# 12V-2A-buck.net
KiCad netlist of a schematic drawn in Altium Designer
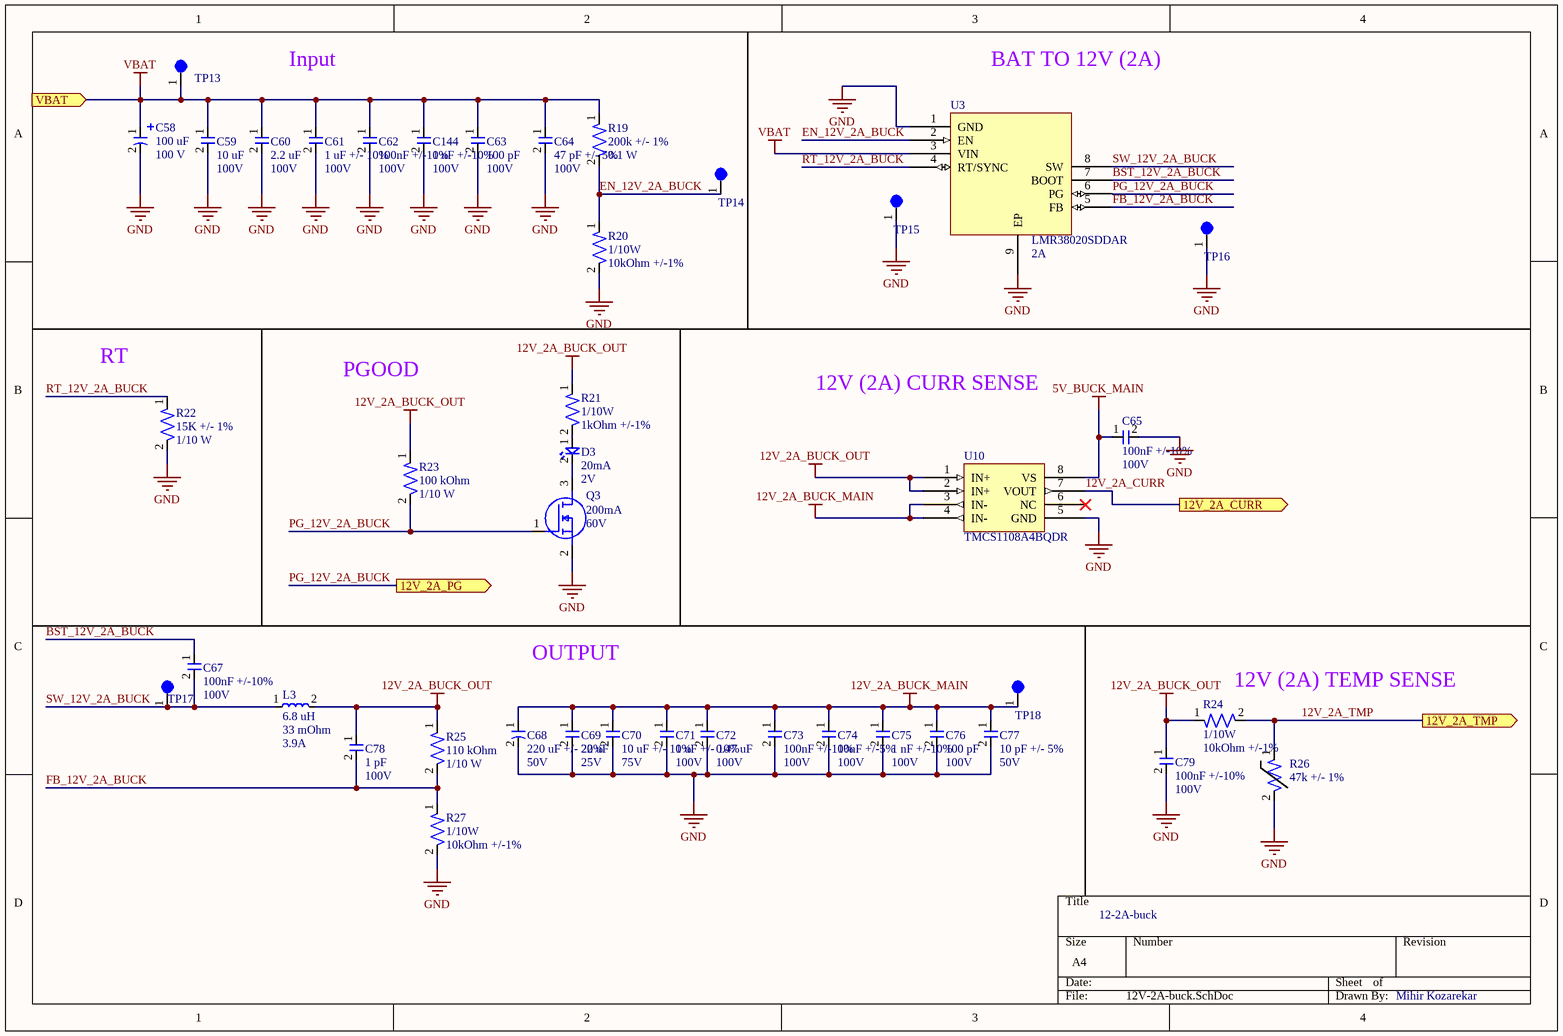
[diagram p0: 12V-2A-buck.SchDoc]

(export (version "E")
  (design (tool "Eeschema 10.0.6"))
  (components
    (comp (ref "C58")
      (value "100SEV100M12.5X16")
      (footprint "ELEC-100U-0001")
      (description "100 µF 100 V Aluminum Electrolytic Capacitors Radial, Can - SMD 2000 Hrs @ 85°C")
      (fields
        (field (name "MANUFACTURER") "Rubycon")
        (field (name "TOLERANCE") "+/- 20%")
        (field (name "CAPACITANCE") "100 uF")
        (field (name "VOLTAGE") "100 V")
      )
      (libsource (lib "MasterLib") (part "ELEC-100U-0001"))
    )
    (comp (ref "C59")
      (value "GRM32EC72A106KE05L")
      (footprint "CAP-1210")
      (description "10 µF ±10% 100V Ceramic Capacitor X7S 1210 (3225 Metric)")
      (fields (field (name "CAPCITANCE") "10 uF") (field (name "VOLTAGE RATING") "100V"))
      (libsource (lib "MasterLib") (part "CAP-10U-0003"))
    )
    (comp (ref "C60")
      (value "CL31B225KCHSNNE")
      (footprint "CAP-1206")
      (description "2.2 µF ±10% 100V Ceramic Capacitor X7R 1206 (3216 Metric)")
      (fields
        (field (name "MANUFACTURER") "Samsung Electro-Mechanics")
        (field (name "TOLERANCE") "+/- 10%")
        (field (name "CAPACITANCE") "2.2 uF")
        (field (name "VOLTAGE") "100V")
      )
      (libsource (lib "MasterLib") (part "CAP-2.2U-0003"))
    )
    (comp (ref "C61")
      (value "CL31B105KCHNNNE")
      (footprint "CAP-1206 - duplicate")
      (description "1 µF ±10% 100V Ceramic Capacitor X7R 1206 (3216 Metric)")
      (fields (field (name "CAPACITANCE") "1 uF +/- 10%") (field (name "VOLTAGE") "100V"))
      (libsource (lib "MasterLib") (part "CAP-1U-0001"))
    )
    (comp (ref "C62")
      (value "CC0603KRX7R0BB104")
      (footprint "CAP-0603")
      (description "CAP CER 0.1UF 100V X7R 0603")
      (fields
        (field (name "MANUFACTURER") "YAGEO")
        (field (name "CAPACITANCE") "100nF +/-10%")
        (field (name "VOLTAGE RATING") "100V")
      )
      (libsource (lib "MasterLib") (part "CAP-100N-0001"))
    )
    (comp (ref "C63")
      (value "0603N101J101CT")
      (footprint "CAP-0603")
      (description "100 pF ±5% 100V Ceramic Capacitor C0G, NP0 0603 (1608 Metric)")
      (fields
        (field (name "TOLERANCE") "+/-5%")
        (field (name "CAPACITANCE") "100 pF")
        (field (name "VOLTAGE") "100V")
      )
      (libsource (lib "MasterLib") (part "CAP-100P-0002"))
    )
    (comp (ref "C64")
      (value "7447798111")
      (footprint "CAP-0603")
      (description "47 pF ±5% 100V Ceramic Capacitor C0G, NP0 0603 (1608 Metric)")
      (fields (field (name "CAPACITANCE") "47 pF +/- 5%") (field (name "VOLTAGE RATING") "100V"))
      (libsource (lib "MasterLib") (part "CAP-47P-0001"))
    )
    (comp (ref "C65")
      (value "CC0603KRX7R0BB104")
      (footprint "CAP-0603")
      (description "CAP CER 0.1UF 100V X7R 0603")
      (fields
        (field (name "MANUFACTURER") "YAGEO")
        (field (name "CAPACITANCE") "100nF +/-10%")
        (field (name "VOLTAGE RATING") "100V")
      )
      (libsource (lib "MasterLib") (part "CAP-100N-0001"))
    )
    (comp (ref "C67")
      (value "CC0603KRX7R0BB104")
      (footprint "CAP-0603")
      (description "CAP CER 0.1UF 100V X7R 0603")
      (fields
        (field (name "MANUFACTURER") "YAGEO")
        (field (name "CAPACITANCE") "100nF +/-10%")
        (field (name "VOLTAGE RATING") "100V")
      )
      (libsource (lib "MasterLib") (part "CAP-100N-0001"))
    )
    (comp (ref "C68")
      (value "50TZV220M10X10.5")
      (footprint "ELEC-220U-0003")
      (description "220 µF 50 V Aluminum Electrolytic Capacitors Radial, Can - SMD 2000 Hrs @ 105°C")
      (fields (field (name "CAPACITANCE") "220 uF +/- 20%") (field (name "VOLTAGE RATING") "50V"))
      (libsource (lib "MasterLib") (part "ELEC-220U-0003"))
    )
    (comp (ref "C69")
      (value "CL32B226KAJNNNE")
      (footprint "CAP-1210")
      (description "22 µF ±10% 25V Ceramic Capacitor X7R 1210 (3225 Metric)")
      (fields
        (field (name "TOLERANCE") "+/- 10%")
        (field (name "CAPACITANCE") "22 uF")
        (field (name "VOLTAGE") "25V")
      )
      (libsource (lib "MasterLib") (part "CAP-22U-0003"))
    )
    (comp (ref "C70")
      (value "C3225X7R1N106K250AC")
      (footprint "CAP-1210")
      (description "10 µF ±10% 75V Ceramic Capacitor X7R 1210 (3225 Metric)")
      (fields (field (name "CAPACITANCE") "10 uF +/- 10%") (field (name "VOLTAGE RATING") "75V"))
      (libsource (lib "MasterLib") (part "CAP-10U-0004"))
    )
    (comp (ref "C71")
      (value "CL31B105KCHNNNE")
      (footprint "CAP-1206 - duplicate")
      (description "1 µF ±10% 100V Ceramic Capacitor X7R 1206 (3216 Metric)")
      (fields (field (name "CAPACITANCE") "1 uF +/- 10%") (field (name "VOLTAGE") "100V"))
      (libsource (lib "MasterLib") (part "CAP-1U-0001"))
    )
    (comp (ref "C72")
      (value "KAM21KR72A474KL")
      (footprint "CAP-0805")
      (description "0.47 µF ±10% 100V Ceramic Capacitor X7R 0805 (2012 Metric)")
      (fields
        (field (name "TOLERANCE") "+/- 10%")
        (field (name "CAPACITANCE") "0.47 uF")
        (field (name "VOLTAGE") "100V")
      )
      (libsource (lib "MasterLib") (part "CAP-0.47U-0001"))
    )
    (comp (ref "C73")
      (value "CC0603KRX7R0BB104")
      (footprint "CAP-0603")
      (description "CAP CER 0.1UF 100V X7R 0603")
      (fields
        (field (name "MANUFACTURER") "YAGEO")
        (field (name "CAPACITANCE") "100nF +/-10%")
        (field (name "VOLTAGE RATING") "100V")
      )
      (libsource (lib "MasterLib") (part "CAP-100N-0001"))
    )
    (comp (ref "C74")
      (value "C1608C0G2A103J080AC")
      (footprint "CAP-0603")
      (description "CAP CER 10000PF 100V C0G 0603")
      (fields
        (field (name "MANUFACTURER") "TDK Corporation")
        (field (name "CAPACITANCE") "10nF +/-5%")
        (field (name "VOLTAGE RATING") "100V")
      )
      (libsource (lib "MasterLib") (part "CAP-10N-0002"))
    )
    (comp (ref "C75")
      (value "C0603Y102K1RAC7867")
      (footprint "CAP-0603")
      (description "1000 pF ±10% 100V Ceramic Capacitor X7R 0603 (1608 Metric)")
      (fields (field (name "CAPACITANCE") "1 nF +/-10%") (field (name "VOLTAGE") "100V"))
      (libsource (lib "MasterLib") (part "CAP-1N-0001"))
    )
    (comp (ref "C76")
      (value "0603N101J101CT")
      (footprint "CAP-0603")
      (description "100 pF ±5% 100V Ceramic Capacitor C0G, NP0 0603 (1608 Metric)")
      (fields
        (field (name "TOLERANCE") "+/-5%")
        (field (name "CAPACITANCE") "100 pF")
        (field (name "VOLTAGE") "100V")
      )
      (libsource (lib "MasterLib") (part "CAP-100P-0002"))
    )
    (comp (ref "C77")
      (value "0603N100J500CT")
      (footprint "CAP-0603")
      (description "10 pF ±5% 50V Ceramic Capacitor C0G, NP0 0603 (1608 Metric)")
      (fields
        (field (name "MANUFACTURER") "Walshin Technology Corporation")
        (field (name "CAPACITANCE") "10 pF +/- 5%")
        (field (name "VOLTAGE RATING") "50V")
      )
      (libsource (lib "MasterLib") (part "CAP-10P-0001"))
    )
    (comp (ref "C78")
      (value "885012006087")
      (footprint "CAP-0603")
      (description "1 pF ±0.25pF 100V Ceramic Capacitor C0G, NP0 0603 (1608 Metric)")
      (fields
        (field (name "TOLERANCE") "+/- 0.25 pF")
        (field (name "CAPACITANCE") "1 pF")
        (field (name "VOLTAGE") "100V")
      )
      (libsource (lib "MasterLib") (part "CAP-1P-0001"))
    )
    (comp (ref "C79")
      (value "CC0603KRX7R0BB104")
      (footprint "CAP-0603")
      (description "CAP CER 0.1UF 100V X7R 0603")
      (fields
        (field (name "MANUFACTURER") "YAGEO")
        (field (name "CAPACITANCE") "100nF +/-10%")
        (field (name "VOLTAGE RATING") "100V")
      )
      (libsource (lib "MasterLib") (part "CAP-100N-0001"))
    )
    (comp (ref "C144")
      (value "C0603Y102K1RAC7867")
      (footprint "CAP-0603")
      (description "1000 pF ±10% 100V Ceramic Capacitor X7R 0603 (1608 Metric)")
      (fields (field (name "CAPACITANCE") "1 nF +/-10%") (field (name "VOLTAGE") "100V"))
      (libsource (lib "MasterLib") (part "CAP-1N-0001"))
    )
    (comp (ref "D3")
      (value "150060AS75000")
      (footprint "LED-0603")
      (description "CAP CER 0.1UF 100V X7R 0603")
      (fields
        (field (name "MANUFACTURER") "Wurth Electronik")
        (field (name "CURRENT RATING") "20mA")
        (field (name "VF") "2V")
      )
      (libsource (lib "MasterLib") (part "LED_Amber_0001"))
    )
    (comp (ref "L3")
      (value "SRN8040-6R8Y")
      (footprint "PWRIND-6.8U-0001")
      (description "6.8 µH Semi-Shielded Drum Core, Wirewound Inductor 3.9 A 33mOhm Max Nonstandard")
      (fields
        (field (name "TOLERANCE") "30%")
        (field (name "INDUCTANCE") "6.8 uH")
        (field (name "DCR") "33 mOhm")
        (field (name "DCI") "3.9A")
      )
      (libsource (lib "MasterLib") (part "PWRIND-6.8U-0001"))
    )
    (comp (ref "Q3")
      (value "T2N7002AK,LM")
      (footprint "NMOS-SOT23-3")
      (description "MOSFET N-CH 60V 200MA SOT23")
      (fields
        (field (name "MANUFACTURER") "Toshiba")
        (field (name "ID-CONTINUOUS") "200mA")
        (field (name "VDS-MAX") "60V")
      )
      (libsource (lib "MasterLib") (part "NMOS-200MA-0001"))
    )
    (comp (ref "R19")
      (value "ERJ-3EKF2003V")
      (footprint "RES-0603")
      (description "200 kOhms ±1% 0.1W, 1/10W Chip Resistor 0603 (1608 Metric) Automotive AEC-Q200 Thick Film")
      (fields
        (field (name "MANUFACTURER") "Panasonic Electronic Components")
        (field (name "RESISTANCE") "200k +/- 1%")
        (field (name "POWER RATING") "0.1 W")
      )
      (libsource (lib "MasterLib") (part "RES-200K-0001"))
    )
    (comp (ref "R20")
      (value "RC0603FR-0710KP")
      (footprint "RES-0603")
      (description "RES SMD 10K OHM 1% 1/10W 0603")
      (fields
        (field (name "MANUFACTURER") "YAGEO")
        (field (name "POWER RATING") "1/10W")
        (field (name "RESISTANCE") "10kOhm +/-1%")
      )
      (libsource (lib "MasterLib") (part "RES-10K-0002"))
    )
    (comp (ref "R21")
      (value "RT0603FRE131KL")
      (footprint "RES-0603")
      (description "1 kOhms ±1% 0.1W, 1/10W Chip Resistor 0603 (1608 Metric) Thin Film")
      (fields
        (field (name "MANUFACTURER") "YAGEO")
        (field (name "POWER RATING") "1/10W")
        (field (name "RESISTANCE") "1kOhm +/-1%")
      )
      (libsource (lib "MasterLib") (part "RES-1K-0002"))
    )
    (comp (ref "R22")
      (value "ERJ-2RKF1502X")
      (footprint "RES-0402")
      (description "15 kOhms ±1% 0.1W, 1/10W Chip Resistor 0402 (1005 Metric) Automotive AEC-Q200 Thick Film")
      (fields (field (name "RES") "15K +/- 1%") (field (name "POWER") "1/10 W"))
      (libsource (lib "MasterLib") (part "RES-15K-0001"))
    )
    (comp (ref "R23")
      (value "RC0603FR-07100KL")
      (footprint "RES-0603")
      (description "100 kOhms ±1% 0.1W, 1/10W Chip Resistor 0603 (1608 Metric) Moisture Resistant Thick Film")
      (fields
        (field (name "TOLERANCE") "+/- 1%")
        (field (name "RESISTANCE") "100 kOhm")
        (field (name "POWER") "1/10 W")
      )
      (libsource (lib "MasterLib") (part "RES-100K-0003"))
    )
    (comp (ref "R24")
      (value "RC0603FR-0710KP")
      (footprint "RES-0603")
      (description "RES SMD 10K OHM 1% 1/10W 0603")
      (fields
        (field (name "MANUFACTURER") "YAGEO")
        (field (name "POWER RATING") "1/10W")
        (field (name "RESISTANCE") "10kOhm +/-1%")
      )
      (libsource (lib "MasterLib") (part "RES-10K-0002"))
    )
    (comp (ref "R25")
      (value "RC0603FR-07110KL")
      (footprint "RES-0603")
      (description "110 kOhms ±1% 0.1W, 1/10W Chip Resistor 0603 (1608 Metric) Moisture Resistant Thick Film")
      (fields
        (field (name "TOLERANCE") "+/- 1%")
        (field (name "RESISTANCE") "110 kOhm")
        (field (name "POWER") "1/10 W")
      )
      (libsource (lib "MasterLib") (part "RES-110K-0001"))
    )
    (comp (ref "R26")
      (value "TMP6431DECR")
      (footprint "RES-0402")
      (description "PTC Thermistor 47 kOhms 0402 (1006 Metric)")
      (fields (field (name "MANUFACTURER") "Texas Instruments") (field (name "RESISTANCE") "47k +/- 1%"))
      (libsource (lib "MasterLib") (part "THERM-47K-0001"))
    )
    (comp (ref "R27")
      (value "RC0603FR-0710KP")
      (footprint "RES-0603")
      (description "RES SMD 10K OHM 1% 1/10W 0603")
      (fields
        (field (name "MANUFACTURER") "YAGEO")
        (field (name "POWER RATING") "1/10W")
        (field (name "RESISTANCE") "10kOhm +/-1%")
      )
      (libsource (lib "MasterLib") (part "RES-10K-0002"))
    )
    (comp (ref "TP13")
      (value "5003")
      (footprint "TEST-POINT-0001")
      (description "Oranange PC Test Point, Miniature Phoisphor Bronze Silver Plating Through Hole Mounting Type")
      (libsource (lib "MasterLib") (part "TEST-POINT-0001"))
    )
    (comp (ref "TP14")
      (value "5003")
      (footprint "TEST-POINT-0001")
      (description "Oranange PC Test Point, Miniature Phoisphor Bronze Silver Plating Through Hole Mounting Type")
      (libsource (lib "MasterLib") (part "TEST-POINT-0001"))
    )
    (comp (ref "TP15")
      (value "5003")
      (footprint "TEST-POINT-0001")
      (description "Oranange PC Test Point, Miniature Phoisphor Bronze Silver Plating Through Hole Mounting Type")
      (libsource (lib "MasterLib") (part "TEST-POINT-0001"))
    )
    (comp (ref "TP16")
      (value "5003")
      (footprint "TEST-POINT-0001")
      (description "Oranange PC Test Point, Miniature Phoisphor Bronze Silver Plating Through Hole Mounting Type")
      (libsource (lib "MasterLib") (part "TEST-POINT-0001"))
    )
    (comp (ref "TP17")
      (value "5003")
      (footprint "TEST-POINT-0001")
      (description "Oranange PC Test Point, Miniature Phoisphor Bronze Silver Plating Through Hole Mounting Type")
      (libsource (lib "MasterLib") (part "TEST-POINT-0001"))
    )
    (comp (ref "TP18")
      (value "5003")
      (footprint "TEST-POINT-0001")
      (description "Oranange PC Test Point, Miniature Phoisphor Bronze Silver Plating Through Hole Mounting Type")
      (libsource (lib "MasterLib") (part "TEST-POINT-0001"))
    )
    (comp (ref "U3")
      (value "LMR38020SDDAR")
      (footprint "IC-8PowerSOIC")
      (description "Buck Switching Regulator IC Positive Adjustable 1V 1 Output 2A 8-PowerSOIC (0.154\", 3.90mm Width)")
      (fields (field (name "CURRENT") "2A"))
      (libsource (lib "MasterLib") (part "IC-BUCK-0007"))
    )
    (comp (ref "U10")
      (value "TMCS1108A4BQDR")
      (footprint "IC-CURRENT-0001")
      (description "Current Sensor 1 Channel Hall Effect Bidirectional 8-SOIC (0.154\", 3.90mm Width)")
      (libsource (lib "MasterLib") (part "IC-CURRENT-0004"))
    )
  )
  (nets
    (net (code "1") (name "/12V_2A_CURR") (class "Default")
      (node (ref "U10") (pin "7") (pinfunction "VOUT_7") (pintype "output"))
    )
    (net (code "2") (name "/12V_2A_TMP") (class "Default")
      (node (ref "R24") (pin "2") (pinfunction "2_2") (pintype "passive"))
      (node (ref "R26") (pin "1") (pinfunction "1_1") (pintype "passive"))
    )
    (net (code "3") (name "/BST_12V_2A_BUCK") (class "Default")
      (node (ref "C67") (pin "1") (pinfunction "1_1") (pintype "passive"))
      (node (ref "U3") (pin "7") (pinfunction "BOOT_7") (pintype "power_in"))
    )
    (net (code "4") (name "/EN_12V_2A_BUCK") (class "Default")
      (node (ref "R19") (pin "2") (pinfunction "2_2") (pintype "passive"))
      (node (ref "R20") (pin "1") (pinfunction "1_1") (pintype "passive"))
      (node (ref "TP14") (pin "1") (pinfunction "0_1") (pintype "passive"))
      (node (ref "U3") (pin "2") (pinfunction "EN_2") (pintype "input"))
    )
    (net (code "5") (name "/FB_12V_2A_BUCK") (class "Default")
      (node (ref "C78") (pin "2") (pinfunction "2_2") (pintype "passive"))
      (node (ref "R25") (pin "2") (pinfunction "2_2") (pintype "passive"))
      (node (ref "R27") (pin "1") (pinfunction "1_1") (pintype "passive"))
      (node (ref "U3") (pin "5") (pinfunction "FB_5") (pintype "bidirectional"))
    )
    (net (code "6") (name "/PG_12V_2A_BUCK") (class "Default")
      (node (ref "Q3") (pin "1") (pinfunction "G_1") (pintype "passive"))
      (node (ref "R23") (pin "2") (pinfunction "2_2") (pintype "passive"))
      (node (ref "U3") (pin "6") (pinfunction "PG_6") (pintype "bidirectional"))
    )
    (net (code "7") (name "/RT_12V_2A_BUCK") (class "Default")
      (node (ref "R22") (pin "1") (pinfunction "1_1") (pintype "passive"))
      (node (ref "U3") (pin "4") (pinfunction "RT/SYNC_4") (pintype "bidirectional"))
    )
    (net (code "8") (name "/SW_12V_2A_BUCK") (class "Default")
      (node (ref "C67") (pin "2") (pinfunction "2_2") (pintype "passive"))
      (node (ref "L3") (pin "1") (pinfunction "1_1") (pintype "passive"))
      (node (ref "TP17") (pin "1") (pinfunction "0_1") (pintype "passive"))
      (node (ref "U3") (pin "8") (pinfunction "SW_8") (pintype "power_in"))
    )
    (net (code "9") (name "5V_BUCK_MAIN") (class "Default")
      (node (ref "C65") (pin "1") (pinfunction "1_1") (pintype "passive"))
      (node (ref "U10") (pin "8") (pinfunction "VS_8") (pintype "power_in"))
    )
    (net (code "10") (name "12V_2A_BUCK_MAIN") (class "Default")
      (node (ref "C68") (pin "1") (pinfunction "1_1") (pintype "passive"))
      (node (ref "C69") (pin "1") (pinfunction "1_1") (pintype "passive"))
      (node (ref "C70") (pin "1") (pinfunction "1_1") (pintype "passive"))
      (node (ref "C71") (pin "1") (pinfunction "1_1") (pintype "passive"))
      (node (ref "C72") (pin "1") (pinfunction "1_1") (pintype "passive"))
      (node (ref "C73") (pin "1") (pinfunction "1_1") (pintype "passive"))
      (node (ref "C74") (pin "1") (pinfunction "1_1") (pintype "passive"))
      (node (ref "C75") (pin "1") (pinfunction "1_1") (pintype "passive"))
      (node (ref "C76") (pin "1") (pinfunction "1_1") (pintype "passive"))
      (node (ref "C77") (pin "1") (pinfunction "1_1") (pintype "passive"))
      (node (ref "TP18") (pin "1") (pinfunction "0_1") (pintype "passive"))
      (node (ref "U10") (pin "3") (pinfunction "IN-_3") (pintype "output"))
      (node (ref "U10") (pin "4") (pinfunction "IN-_4") (pintype "output"))
    )
    (net (code "11") (name "12V_2A_BUCK_OUT") (class "Default")
      (node (ref "C78") (pin "1") (pinfunction "1_1") (pintype "passive"))
      (node (ref "C79") (pin "1") (pinfunction "1_1") (pintype "passive"))
      (node (ref "L3") (pin "2") (pinfunction "2_2") (pintype "passive"))
      (node (ref "R21") (pin "1") (pinfunction "1_1") (pintype "passive"))
      (node (ref "R23") (pin "1") (pinfunction "1_1") (pintype "passive"))
      (node (ref "R24") (pin "1") (pinfunction "1_1") (pintype "passive"))
      (node (ref "R25") (pin "1") (pinfunction "1_1") (pintype "passive"))
      (node (ref "U10") (pin "1") (pinfunction "IN+_1") (pintype "input"))
      (node (ref "U10") (pin "2") (pinfunction "IN+_2") (pintype "input"))
    )
    (net (code "12") (name "GND") (class "Default")
      (node (ref "C144") (pin "2") (pinfunction "2_2") (pintype "passive"))
      (node (ref "C58") (pin "2") (pinfunction "2_2") (pintype "passive"))
      (node (ref "C59") (pin "2") (pinfunction "2_2") (pintype "passive"))
      (node (ref "C60") (pin "2") (pinfunction "2_2") (pintype "passive"))
      (node (ref "C61") (pin "2") (pinfunction "2_2") (pintype "passive"))
      (node (ref "C62") (pin "2") (pinfunction "2_2") (pintype "passive"))
      (node (ref "C63") (pin "2") (pinfunction "2_2") (pintype "passive"))
      (node (ref "C64") (pin "2") (pinfunction "2_2") (pintype "passive"))
      (node (ref "C65") (pin "2") (pinfunction "2_2") (pintype "passive"))
      (node (ref "C68") (pin "2") (pinfunction "2_2") (pintype "passive"))
      (node (ref "C69") (pin "2") (pinfunction "2_2") (pintype "passive"))
      (node (ref "C70") (pin "2") (pinfunction "2_2") (pintype "passive"))
      (node (ref "C71") (pin "2") (pinfunction "2_2") (pintype "passive"))
      (node (ref "C72") (pin "2") (pinfunction "2_2") (pintype "passive"))
      (node (ref "C73") (pin "2") (pinfunction "2_2") (pintype "passive"))
      (node (ref "C74") (pin "2") (pinfunction "2_2") (pintype "passive"))
      (node (ref "C75") (pin "2") (pinfunction "2_2") (pintype "passive"))
      (node (ref "C76") (pin "2") (pinfunction "2_2") (pintype "passive"))
      (node (ref "C77") (pin "2") (pinfunction "2_2") (pintype "passive"))
      (node (ref "C79") (pin "2") (pinfunction "2_2") (pintype "passive"))
      (node (ref "Q3") (pin "2") (pinfunction "S_2") (pintype "passive"))
      (node (ref "R20") (pin "2") (pinfunction "2_2") (pintype "passive"))
      (node (ref "R22") (pin "2") (pinfunction "2_2") (pintype "passive"))
      (node (ref "R26") (pin "2") (pinfunction "2_2") (pintype "passive"))
      (node (ref "R27") (pin "2") (pinfunction "2_2") (pintype "passive"))
      (node (ref "TP15") (pin "1") (pinfunction "0_1") (pintype "passive"))
      (node (ref "TP16") (pin "1") (pinfunction "0_1") (pintype "passive"))
      (node (ref "U10") (pin "5") (pinfunction "GND_5") (pintype "power_in"))
      (node (ref "U3") (pin "1") (pinfunction "GND_1") (pintype "power_in"))
      (node (ref "U3") (pin "9") (pinfunction "EP_9") (pintype "power_in"))
    )
    (net (code "13") (name "Net-(D3-Pad1)") (class "Default")
      (node (ref "D3") (pin "1") (pinfunction "1_1") (pintype "passive"))
      (node (ref "R21") (pin "2") (pinfunction "2_2") (pintype "passive"))
    )
    (net (code "14") (name "Net-(Q3-D)") (class "Default")
      (node (ref "D3") (pin "2") (pinfunction "2_2") (pintype "passive"))
      (node (ref "Q3") (pin "3") (pinfunction "D_3") (pintype "passive"))
    )
    (net (code "15") (name "VBAT") (class "Default")
      (node (ref "C144") (pin "1") (pinfunction "1_1") (pintype "passive"))
      (node (ref "C58") (pin "1") (pinfunction "1_1") (pintype "passive"))
      (node (ref "C59") (pin "1") (pinfunction "1_1") (pintype "passive"))
      (node (ref "C60") (pin "1") (pinfunction "1_1") (pintype "passive"))
      (node (ref "C61") (pin "1") (pinfunction "1_1") (pintype "passive"))
      (node (ref "C62") (pin "1") (pinfunction "1_1") (pintype "passive"))
      (node (ref "C63") (pin "1") (pinfunction "1_1") (pintype "passive"))
      (node (ref "C64") (pin "1") (pinfunction "1_1") (pintype "passive"))
      (node (ref "R19") (pin "1") (pinfunction "1_1") (pintype "passive"))
      (node (ref "TP13") (pin "1") (pinfunction "0_1") (pintype "passive"))
      (node (ref "U3") (pin "3") (pinfunction "VIN_3") (pintype "power_in"))
    )
    (net (code "16") (name "unconnected-(U10-NC-Pad6)") (class "Default")
      (node (ref "U10") (pin "6") (pinfunction "NC_6") (pintype "tri_state+no_connect"))
    )
  )
)
